# CONNECTOR.net
KiCad netlist of a schematic drawn in Altium Designer
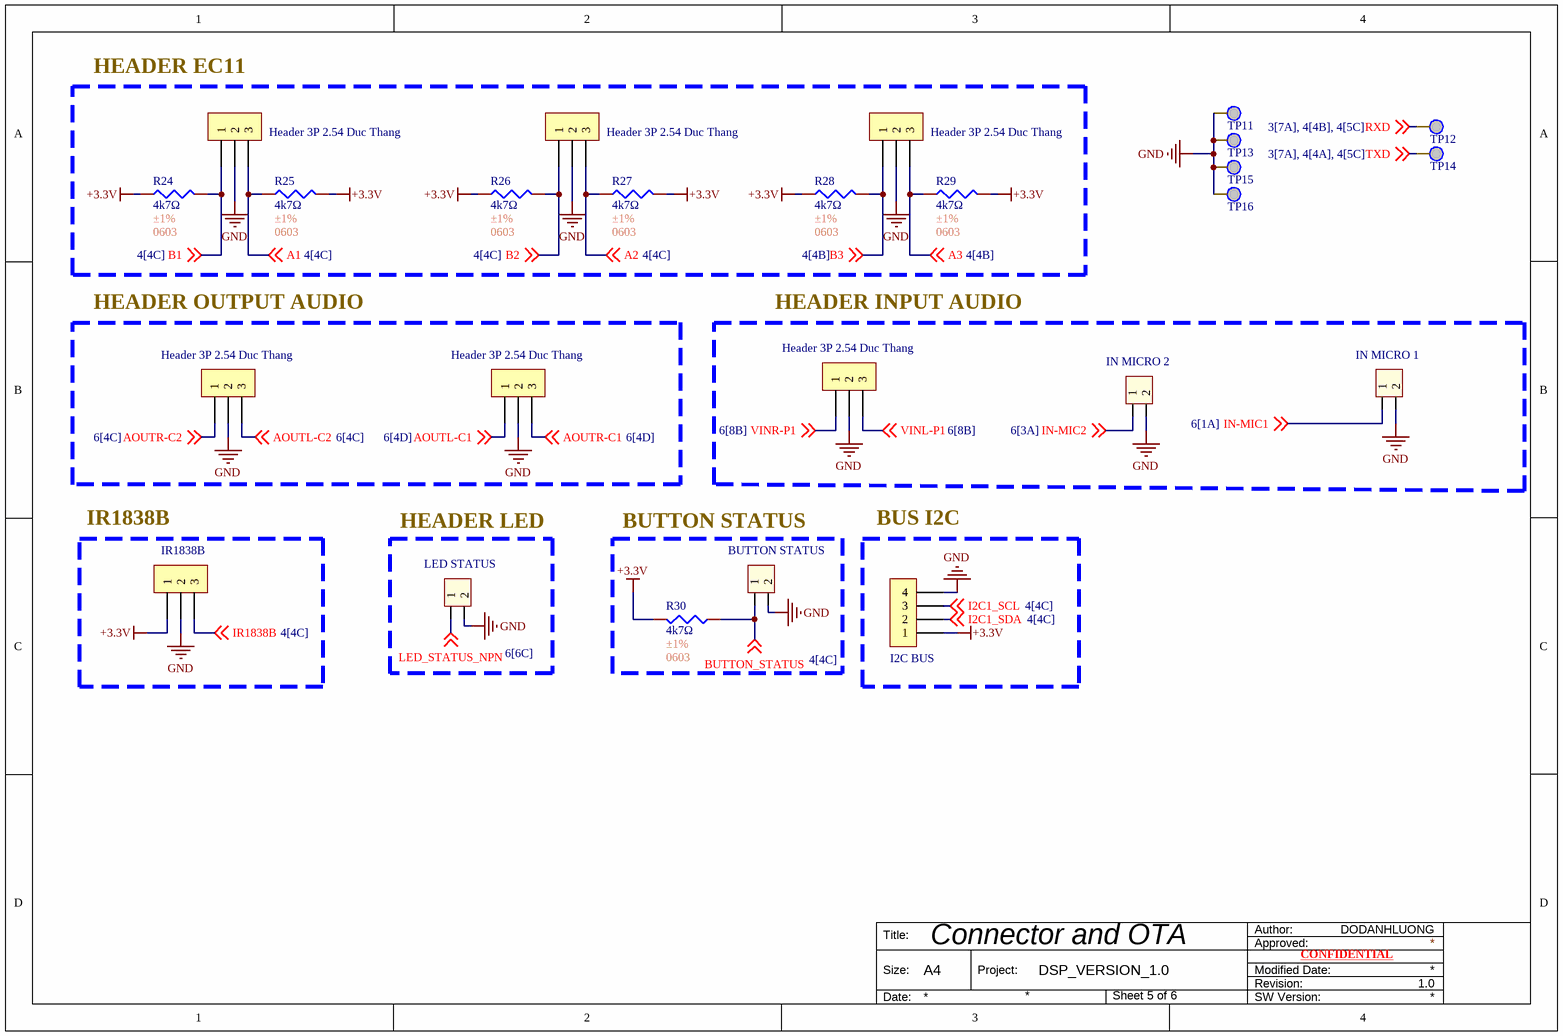
[diagram p0: CONNECTOR.SchDoc]

(export (version "E")
  (design (tool "Eeschema 10.0.6"))
  (components
    (comp (ref "H1")
      (value "Header 3P 2.54 Duc Thang")
      (footprint "XH2.54M-3")
      (description "Cắm")
      (libsource (lib "Header") (part "Header 3P 2.54 Duc Thang"))
    )
    (comp (ref "H2")
      (value "Header 3P 2.54 Duc Thang")
      (footprint "XH2.54M-3")
      (description "Cắm")
      (libsource (lib "Header") (part "Header 3P 2.54 Duc Thang"))
    )
    (comp (ref "H3")
      (value "Header 3P 2.54 Duc Thang")
      (footprint "XH2.54M-3")
      (description "Cắm")
      (libsource (lib "Header") (part "Header 3P 2.54 Duc Thang"))
    )
    (comp (ref "H4")
      (value "Header 3P 2.54 Duc Thang")
      (footprint "XH2.54M-3")
      (description "Cắm")
      (libsource (lib "Header") (part "Header 3P 2.54 Duc Thang"))
    )
    (comp (ref "H5")
      (value "Header 3P 2.54 Duc Thang")
      (footprint "XH2.54M-3")
      (description "Cắm")
      (libsource (lib "Header") (part "Header 3P 2.54 Duc Thang"))
    )
    (comp (ref "H6")
      (value "Header 3P 2.54 Duc Thang")
      (footprint "XH2.54M-3")
      (description "Cắm")
      (libsource (lib "Header") (part "Header 3P 2.54 Duc Thang"))
    )
    (comp (ref "H7")
      (value "IN MICRO 1")
      (footprint "XH2.54M-2")
      (description "Cắm")
      (libsource (lib "Header") (part "Header 2P 2.54 Duc Thang"))
    )
    (comp (ref "H8")
      (value "IN MICRO 2")
      (footprint "XH2.54M-2")
      (description "Cắm")
      (libsource (lib "Header") (part "Header 2P 2.54 Duc Thang"))
    )
    (comp (ref "H9")
      (value "IR1838B")
      (footprint "XH2.54M-3")
      (description "Cắm")
      (libsource (lib "Header") (part "Header 3P 2.54 Duc Thang"))
    )
    (comp (ref "H10")
      (value "BUTTON STATUS")
      (footprint "XH2.54M-2")
      (description "Cắm")
      (libsource (lib "Header") (part "Header 2P 2.54 Duc Thang"))
    )
    (comp (ref "H11")
      (value "LED STATUS")
      (footprint "XH2.54M-2")
      (description "Cắm")
      (libsource (lib "Header") (part "Header 2P 2.54 Duc Thang"))
    )
    (comp (ref "H12")
      (value "I2C BUS")
      (footprint "XH2.54M-4")
      (description "Cắm")
      (libsource (lib "Header") (part "Header 4P 2.54 Duc Thang"))
    )
    (comp (ref "R24")
      (value "4k7Ω")
      (footprint "R0603")
      (description "62.5mW Thick Film Resistor 50V ±1% ±200ppm/℃ 10Ω 0402 Chip Resistor - Surface Mount ROHS")
      (fields
        (field (name "MANUFACTURER") "YAGEO")
        (field (name "MFR. PART #") "RC0402FR-0710RL")
        (field (name "TOLERANCE") "±1%")
        (field (name "PACKAGE") "0603")
      )
      (libsource (lib "Resistor") (part "R0603_4k7Ω_±1%"))
    )
    (comp (ref "R25")
      (value "4k7Ω")
      (footprint "R0603")
      (description "62.5mW Thick Film Resistor 50V ±1% ±200ppm/℃ 10Ω 0402 Chip Resistor - Surface Mount ROHS")
      (fields
        (field (name "MANUFACTURER") "YAGEO")
        (field (name "MFR. PART #") "RC0402FR-0710RL")
        (field (name "TOLERANCE") "±1%")
        (field (name "PACKAGE") "0603")
      )
      (libsource (lib "Resistor") (part "R0603_4k7Ω_±1%"))
    )
    (comp (ref "R26")
      (value "4k7Ω")
      (footprint "R0603")
      (description "62.5mW Thick Film Resistor 50V ±1% ±200ppm/℃ 10Ω 0402 Chip Resistor - Surface Mount ROHS")
      (fields
        (field (name "MANUFACTURER") "YAGEO")
        (field (name "MFR. PART #") "RC0402FR-0710RL")
        (field (name "TOLERANCE") "±1%")
        (field (name "PACKAGE") "0603")
      )
      (libsource (lib "Resistor") (part "R0603_4k7Ω_±1%"))
    )
    (comp (ref "R27")
      (value "4k7Ω")
      (footprint "R0603")
      (description "62.5mW Thick Film Resistor 50V ±1% ±200ppm/℃ 10Ω 0402 Chip Resistor - Surface Mount ROHS")
      (fields
        (field (name "MANUFACTURER") "YAGEO")
        (field (name "MFR. PART #") "RC0402FR-0710RL")
        (field (name "TOLERANCE") "±1%")
        (field (name "PACKAGE") "0603")
      )
      (libsource (lib "Resistor") (part "R0603_4k7Ω_±1%"))
    )
    (comp (ref "R28")
      (value "4k7Ω")
      (footprint "R0603")
      (description "62.5mW Thick Film Resistor 50V ±1% ±200ppm/℃ 10Ω 0402 Chip Resistor - Surface Mount ROHS")
      (fields
        (field (name "MANUFACTURER") "YAGEO")
        (field (name "MFR. PART #") "RC0402FR-0710RL")
        (field (name "TOLERANCE") "±1%")
        (field (name "PACKAGE") "0603")
      )
      (libsource (lib "Resistor") (part "R0603_4k7Ω_±1%"))
    )
    (comp (ref "R29")
      (value "4k7Ω")
      (footprint "R0603")
      (description "62.5mW Thick Film Resistor 50V ±1% ±200ppm/℃ 10Ω 0402 Chip Resistor - Surface Mount ROHS")
      (fields
        (field (name "MANUFACTURER") "YAGEO")
        (field (name "MFR. PART #") "RC0402FR-0710RL")
        (field (name "TOLERANCE") "±1%")
        (field (name "PACKAGE") "0603")
      )
      (libsource (lib "Resistor") (part "R0603_4k7Ω_±1%"))
    )
    (comp (ref "R30")
      (value "4k7Ω")
      (footprint "R0603")
      (description "62.5mW Thick Film Resistor 50V ±1% ±200ppm/℃ 10Ω 0402 Chip Resistor - Surface Mount ROHS")
      (fields
        (field (name "MANUFACTURER") "YAGEO")
        (field (name "MFR. PART #") "RC0402FR-0710RL")
        (field (name "TOLERANCE") "±1%")
        (field (name "PACKAGE") "0603")
      )
      (libsource (lib "Resistor") (part "R0603_4k7Ω_±1%"))
    )
    (comp (ref "TP11") (value "TP") (footprint "TP") (libsource (lib "Other") (part "TP")))
    (comp (ref "TP12") (value "TP") (footprint "TP") (libsource (lib "Other") (part "TP")))
    (comp (ref "TP13") (value "TP") (footprint "TP") (libsource (lib "Other") (part "TP")))
    (comp (ref "TP14") (value "TP") (footprint "TP") (libsource (lib "Other") (part "TP")))
    (comp (ref "TP15") (value "TP") (footprint "TP") (libsource (lib "Other") (part "TP")))
    (comp (ref "TP16") (value "TP") (footprint "TP") (libsource (lib "Other") (part "TP")))
  )
  (nets
    (net (code "1") (name "+3.3V") (class "Default")
      (node (ref "H12") (pin "1") (pinfunction "1_1") (pintype "passive"))
      (node (ref "H9") (pin "1") (pinfunction "1_1") (pintype "passive"))
      (node (ref "R24") (pin "1") (pinfunction "1_1") (pintype "passive"))
      (node (ref "R25") (pin "2") (pinfunction "2_2") (pintype "passive"))
      (node (ref "R26") (pin "1") (pinfunction "1_1") (pintype "passive"))
      (node (ref "R27") (pin "2") (pinfunction "2_2") (pintype "passive"))
      (node (ref "R28") (pin "1") (pinfunction "1_1") (pintype "passive"))
      (node (ref "R29") (pin "2") (pinfunction "2_2") (pintype "passive"))
      (node (ref "R30") (pin "2") (pinfunction "2_2") (pintype "passive"))
    )
    (net (code "2") (name "A1") (class "Default")
      (node (ref "H1") (pin "3") (pinfunction "3_3") (pintype "passive"))
      (node (ref "R25") (pin "1") (pinfunction "1_1") (pintype "passive"))
    )
    (net (code "3") (name "A2") (class "Default")
      (node (ref "H2") (pin "3") (pinfunction "3_3") (pintype "passive"))
      (node (ref "R27") (pin "1") (pinfunction "1_1") (pintype "passive"))
    )
    (net (code "4") (name "A3") (class "Default")
      (node (ref "H3") (pin "3") (pinfunction "3_3") (pintype "passive"))
      (node (ref "R29") (pin "1") (pinfunction "1_1") (pintype "passive"))
    )
    (net (code "5") (name "AOUTL-C1") (class "Default")
      (node (ref "H6") (pin "1") (pinfunction "1_1") (pintype "passive"))
    )
    (net (code "6") (name "AOUTL-C2") (class "Default")
      (node (ref "H5") (pin "3") (pinfunction "3_3") (pintype "passive"))
    )
    (net (code "7") (name "AOUTR-C1") (class "Default")
      (node (ref "H6") (pin "3") (pinfunction "3_3") (pintype "passive"))
    )
    (net (code "8") (name "AOUTR-C2") (class "Default")
      (node (ref "H5") (pin "1") (pinfunction "1_1") (pintype "passive"))
    )
    (net (code "9") (name "B1") (class "Default")
      (node (ref "H1") (pin "1") (pinfunction "1_1") (pintype "passive"))
      (node (ref "R24") (pin "2") (pinfunction "2_2") (pintype "passive"))
    )
    (net (code "10") (name "B2") (class "Default")
      (node (ref "H2") (pin "1") (pinfunction "1_1") (pintype "passive"))
      (node (ref "R26") (pin "2") (pinfunction "2_2") (pintype "passive"))
    )
    (net (code "11") (name "B3") (class "Default")
      (node (ref "H3") (pin "1") (pinfunction "1_1") (pintype "passive"))
      (node (ref "R28") (pin "2") (pinfunction "2_2") (pintype "passive"))
    )
    (net (code "12") (name "BUTTON_STATUS") (class "Default")
      (node (ref "H10") (pin "1") (pinfunction "1_1") (pintype "passive"))
      (node (ref "R30") (pin "1") (pinfunction "1_1") (pintype "passive"))
    )
    (net (code "13") (name "GND") (class "Default")
      (node (ref "H1") (pin "2") (pinfunction "2_2") (pintype "passive"))
      (node (ref "H10") (pin "2") (pinfunction "2_2") (pintype "passive"))
      (node (ref "H11") (pin "2") (pinfunction "2_2") (pintype "passive"))
      (node (ref "H12") (pin "4") (pinfunction "4_4") (pintype "passive"))
      (node (ref "H2") (pin "2") (pinfunction "2_2") (pintype "passive"))
      (node (ref "H3") (pin "2") (pinfunction "2_2") (pintype "passive"))
      (node (ref "H4") (pin "2") (pinfunction "2_2") (pintype "passive"))
      (node (ref "H5") (pin "2") (pinfunction "2_2") (pintype "passive"))
      (node (ref "H6") (pin "2") (pinfunction "2_2") (pintype "passive"))
      (node (ref "H7") (pin "2") (pinfunction "2_2") (pintype "passive"))
      (node (ref "H8") (pin "2") (pinfunction "2_2") (pintype "passive"))
      (node (ref "H9") (pin "2") (pinfunction "2_2") (pintype "passive"))
      (node (ref "TP11") (pin "1") (pinfunction "1_1") (pintype "passive"))
      (node (ref "TP13") (pin "1") (pinfunction "1_1") (pintype "passive"))
      (node (ref "TP15") (pin "1") (pinfunction "1_1") (pintype "passive"))
      (node (ref "TP16") (pin "1") (pinfunction "1_1") (pintype "passive"))
    )
    (net (code "14") (name "I2C1_SCL") (class "Default")
      (node (ref "H12") (pin "3") (pinfunction "3_3") (pintype "passive"))
    )
    (net (code "15") (name "I2C1_SDA") (class "Default")
      (node (ref "H12") (pin "2") (pinfunction "2_2") (pintype "passive"))
    )
    (net (code "16") (name "IN-MIC1") (class "Default")
      (node (ref "H7") (pin "1") (pinfunction "1_1") (pintype "passive"))
    )
    (net (code "17") (name "IN-MIC2") (class "Default")
      (node (ref "H8") (pin "1") (pinfunction "1_1") (pintype "passive"))
    )
    (net (code "18") (name "IR1838B") (class "Default")
      (node (ref "H9") (pin "3") (pinfunction "3_3") (pintype "passive"))
    )
    (net (code "19") (name "LED_STATUS_NPN") (class "Default")
      (node (ref "H11") (pin "1") (pinfunction "1_1") (pintype "passive"))
    )
    (net (code "20") (name "RXD") (class "Default")
      (node (ref "TP12") (pin "1") (pinfunction "1_1") (pintype "passive"))
    )
    (net (code "21") (name "TXD") (class "Default")
      (node (ref "TP14") (pin "1") (pinfunction "1_1") (pintype "passive"))
    )
    (net (code "22") (name "VINL-P1") (class "Default")
      (node (ref "H4") (pin "3") (pinfunction "3_3") (pintype "passive"))
    )
    (net (code "23") (name "VINR-P1") (class "Default")
      (node (ref "H4") (pin "1") (pinfunction "1_1") (pintype "passive"))
    )
  )
)
